# sparkfun-nrf52832-breakout.net
KiCad netlist of a schematic drawn in EAGLE
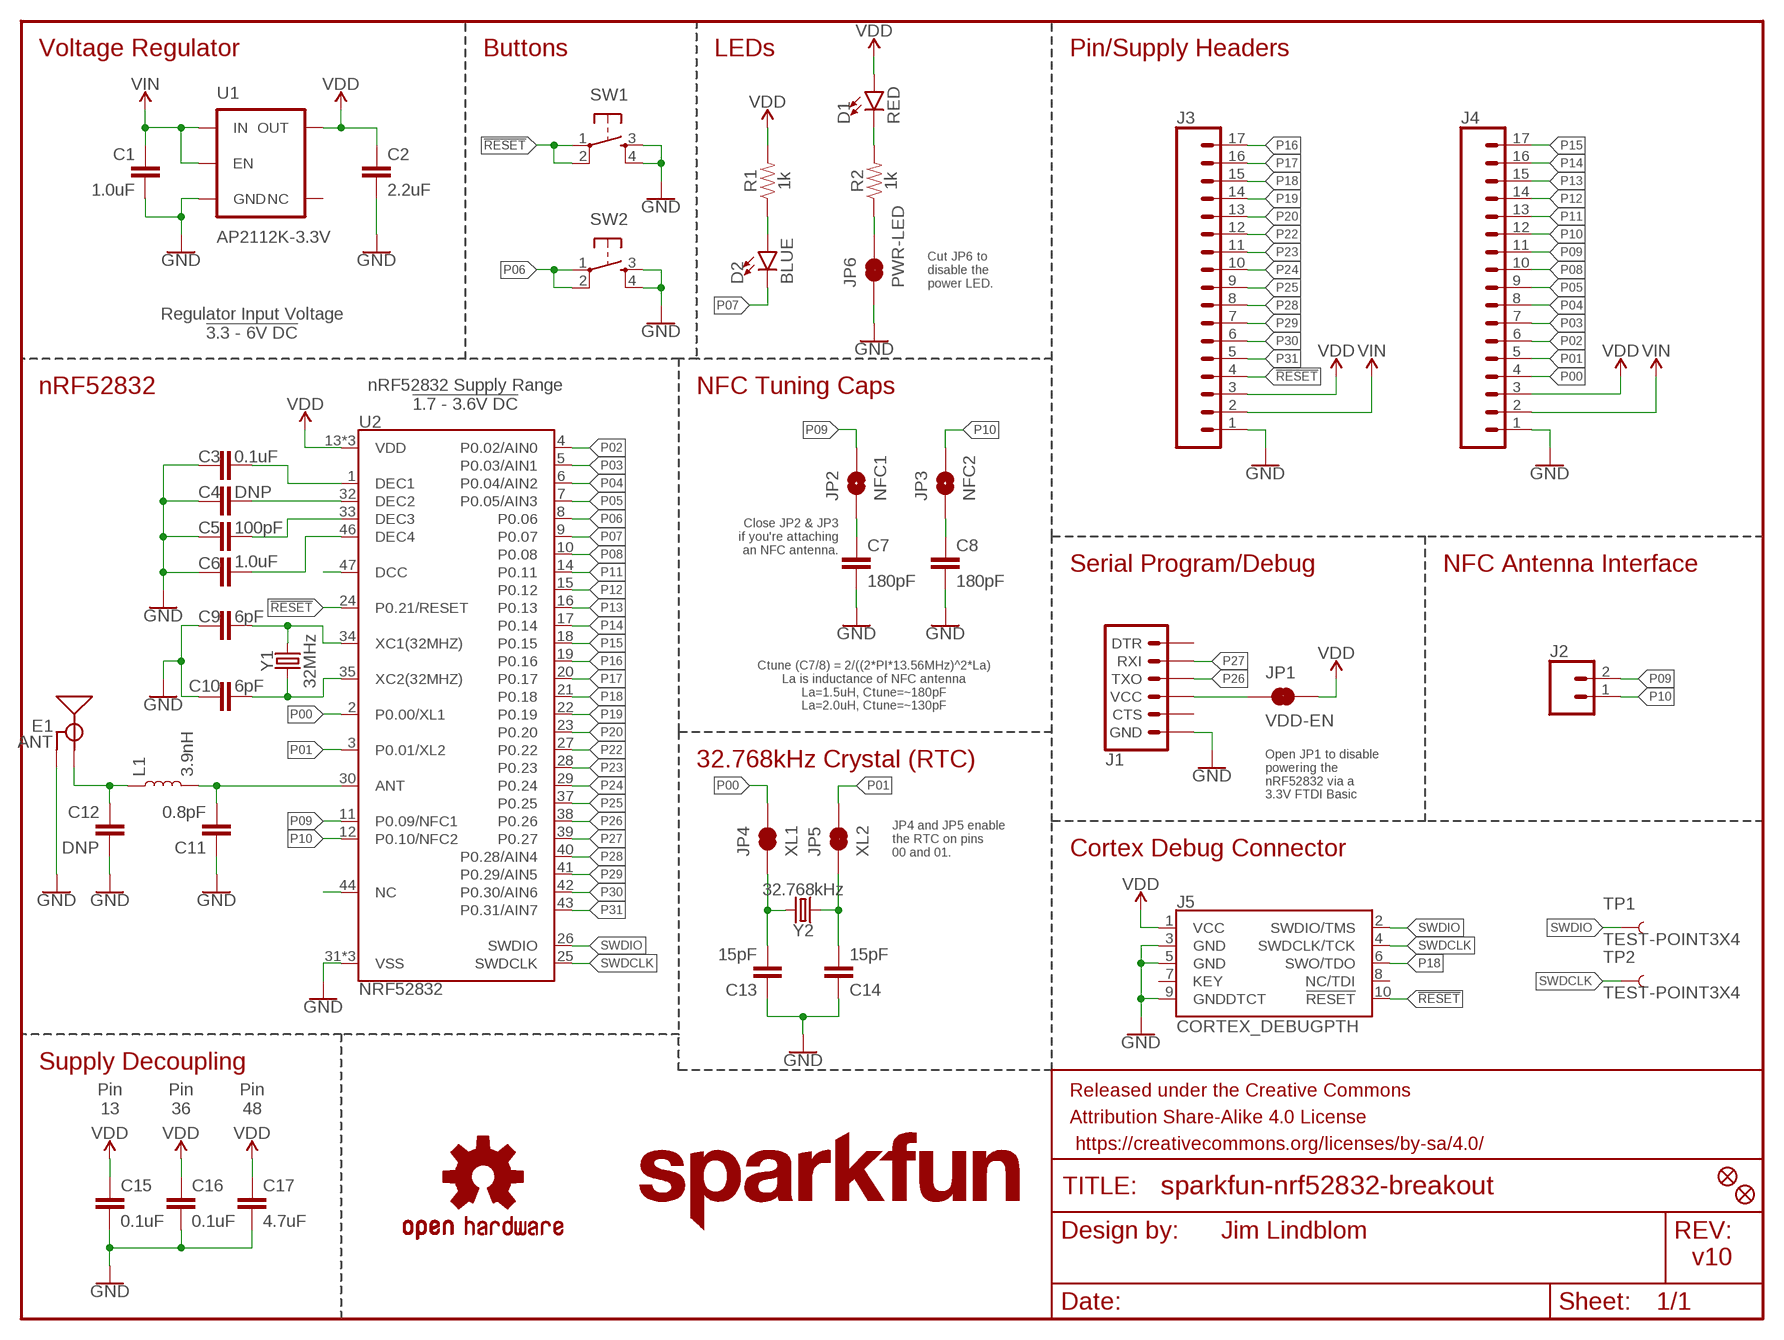
[diagram p0: schematic, sheet 1]

(export (version "E")
  (design (tool "Eeschema 10.0.6"))
  (components
    (comp (ref "C1")
      (value "1.0uF")
      (footprint "eagle-import:0603")
      (libsource (lib "eagle-import") (part "1.0UF-0603-16V-10%"))
    )
    (comp (ref "C2")
      (value "2.2uF")
      (footprint "eagle-import:0603")
      (libsource (lib "eagle-import") (part "2.2UF-0603-10V-20%"))
    )
    (comp (ref "C3")
      (value "0.1uF")
      (footprint "eagle-import:0402")
      (libsource (lib "eagle-import") (part "0.1UF-0402-16V-10%"))
    )
    (comp (ref "C4")
      (value "DNP")
      (footprint "eagle-import:0402")
      (libsource (lib "eagle-import") (part "CAP0402"))
    )
    (comp (ref "C5")
      (value "100pF")
      (footprint "eagle-import:0402")
      (libsource (lib "eagle-import") (part "100PF-0402-50V-5%"))
    )
    (comp (ref "C6")
      (value "1.0uF")
      (footprint "eagle-import:0402")
      (libsource (lib "eagle-import") (part "1.0UF-0402-16V-10%"))
    )
    (comp (ref "C7")
      (value "180pF")
      (footprint "eagle-import:0603")
      (libsource (lib "eagle-import") (part "180PF-0603-50V-5%"))
    )
    (comp (ref "C8")
      (value "180pF")
      (footprint "eagle-import:0603")
      (libsource (lib "eagle-import") (part "180PF-0603-50V-5%"))
    )
    (comp (ref "C9")
      (value "6pF")
      (footprint "eagle-import:0402")
      (libsource (lib "eagle-import") (part "6PF-0402-50V-0.5%"))
    )
    (comp (ref "C10")
      (value "6pF")
      (footprint "eagle-import:0402")
      (libsource (lib "eagle-import") (part "6PF-0402-50V-0.5%"))
    )
    (comp (ref "C11")
      (value "0.8pF")
      (footprint "eagle-import:0402")
      (libsource (lib "eagle-import") (part "0.8PF-0402-50V-0.1PF"))
    )
    (comp (ref "C12")
      (value "DNP")
      (footprint "eagle-import:0402")
      (libsource (lib "eagle-import") (part "CAP0402"))
    )
    (comp (ref "C13")
      (value "15pF")
      (footprint "eagle-import:0402")
      (libsource (lib "eagle-import") (part "15PF-0402-50V-5%"))
    )
    (comp (ref "C14")
      (value "15pF")
      (footprint "eagle-import:0402")
      (libsource (lib "eagle-import") (part "15PF-0402-50V-5%"))
    )
    (comp (ref "C15")
      (value "0.1uF")
      (footprint "eagle-import:0402")
      (libsource (lib "eagle-import") (part "0.1UF-0402-16V-10%"))
    )
    (comp (ref "C16")
      (value "0.1uF")
      (footprint "eagle-import:0402")
      (libsource (lib "eagle-import") (part "0.1UF-0402-16V-10%"))
    )
    (comp (ref "C17")
      (value "4.7uF")
      (footprint "eagle-import:0603")
      (libsource (lib "eagle-import") (part "4.7UF0603"))
    )
    (comp (ref "D1")
      (value "RED")
      (footprint "eagle-import:LED-0603")
      (libsource (lib "eagle-import") (part "LED-RED0603"))
    )
    (comp (ref "D2")
      (value "BLUE")
      (footprint "eagle-import:LED-0603")
      (libsource (lib "eagle-import") (part "LED-BLUE0603"))
    )
    (comp (ref "E1")
      (value "ANT")
      (footprint "eagle-import:TRACE_ANTENNA_2.4GHZ_15.2MM")
      (libsource (lib "eagle-import") (part "ANTENNA-GROUNDEDTRACE-15.2MM"))
    )
    (comp (ref "FD1")
      (value "FIDUCIALUFIDUCIAL")
      (footprint "eagle-import:FIDUCIAL-MICRO")
      (libsource (lib "eagle-import") (part "FIDUCIALUFIDUCIAL"))
    )
    (comp (ref "FD2")
      (value "FIDUCIALUFIDUCIAL")
      (footprint "eagle-import:FIDUCIAL-MICRO")
      (libsource (lib "eagle-import") (part "FIDUCIALUFIDUCIAL"))
    )
    (comp (ref "FRAME1")
      (value "FRAME-LETTER")
      (footprint "eagle-import:CREATIVE_COMMONS")
      (libsource (lib "eagle-import") (part "FRAME-LETTER"))
    )
    (comp (ref "J1")
      (value "ARDUINO_SERIAL_PROGRAMPTH")
      (footprint "eagle-import:1X06")
      (libsource (lib "eagle-import") (part "ARDUINO_SERIAL_PROGRAMPTH"))
    )
    (comp (ref "J2")
      (value "CONN_02PTH")
      (footprint "eagle-import:1X02")
      (libsource (lib "eagle-import") (part "CONN_02PTH"))
    )
    (comp (ref "J3")
      (value "CONN_17")
      (footprint "eagle-import:1X17")
      (libsource (lib "eagle-import") (part "CONN_17"))
    )
    (comp (ref "J4")
      (value "CONN_17")
      (footprint "eagle-import:1X17")
      (libsource (lib "eagle-import") (part "CONN_17"))
    )
    (comp (ref "J5")
      (value "CORTEX_DEBUGPTH")
      (footprint "eagle-import:2X5-PTH-1.27MM")
      (libsource (lib "eagle-import") (part "CORTEX_DEBUGPTH"))
    )
    (comp (ref "JP1")
      (value "VDD-EN")
      (footprint "eagle-import:SMT-JUMPER_2_NC_TRACE_SILK")
      (libsource (lib "eagle-import") (part "JUMPER-SMT_2_NC_TRACE_SILK"))
    )
    (comp (ref "JP2")
      (value "NFC1")
      (footprint "eagle-import:SMT-JUMPER_2_NO_SILK")
      (libsource (lib "eagle-import") (part "JUMPER-SMT_2_NO_SILK"))
    )
    (comp (ref "JP3")
      (value "NFC2")
      (footprint "eagle-import:SMT-JUMPER_2_NO_SILK")
      (libsource (lib "eagle-import") (part "JUMPER-SMT_2_NO_SILK"))
    )
    (comp (ref "JP4")
      (value "XL1")
      (footprint "eagle-import:PAD-JUMPER-2-NC_BY_TRACE_YES_SILK")
      (libsource (lib "eagle-import") (part "JUMPER-PAD-2-NC_BY_TRACE"))
    )
    (comp (ref "JP5")
      (value "XL2")
      (footprint "eagle-import:PAD-JUMPER-2-NC_BY_TRACE_YES_SILK")
      (libsource (lib "eagle-import") (part "JUMPER-PAD-2-NC_BY_TRACE"))
    )
    (comp (ref "JP6")
      (value "PWR-LED")
      (footprint "eagle-import:PAD-JUMPER-2-NC_BY_TRACE_YES_SILK")
      (libsource (lib "eagle-import") (part "JUMPER-PAD-2-NC_BY_TRACE"))
    )
    (comp (ref "L1")
      (value "3.9nH")
      (footprint "eagle-import:0402")
      (libsource (lib "eagle-import") (part "INDUCTOR-0402-3.9NH"))
    )
    (comp (ref "LOGO1")
      (value "OSHW-LOGOMINI")
      (footprint "eagle-import:OSHW-LOGO-MINI")
      (libsource (lib "eagle-import") (part "OSHW-LOGOMINI"))
    )
    (comp (ref "LOGO2")
      (value "SFE_LOGO_NAME.1_INCH")
      (footprint "eagle-import:SFE_LOGO_NAME_.1")
      (libsource (lib "eagle-import") (part "SFE_LOGO_NAME.1_INCH"))
    )
    (comp (ref "LOGO3")
      (value "SFE_LOGO_NAME.1_INCH")
      (footprint "eagle-import:SFE_LOGO_NAME_.1")
      (libsource (lib "eagle-import") (part "SFE_LOGO_NAME.1_INCH"))
    )
    (comp (ref "R1")
      (value "1k")
      (footprint "eagle-import:0603")
      (libsource (lib "eagle-import") (part "1KOHM-0603-1/10W-1%"))
    )
    (comp (ref "R2")
      (value "1k")
      (footprint "eagle-import:0603")
      (libsource (lib "eagle-import") (part "1KOHM-0603-1/10W-1%"))
    )
    (comp (ref "SW1")
      (value "SWITCH_SPST_4_PINRECT")
      (footprint "eagle-import:TACTILE_SWITCH_SMD_4.6X2.8MM")
      (libsource (lib "eagle-import") (part "SWITCH_SPST_4_PINRECT"))
    )
    (comp (ref "SW2")
      (value "SWITCH_SPST_4_PINRECT")
      (footprint "eagle-import:TACTILE_SWITCH_SMD_4.6X2.8MM")
      (libsource (lib "eagle-import") (part "SWITCH_SPST_4_PINRECT"))
    )
    (comp (ref "TP1")
      (value "TEST-POINT3X4")
      (footprint "eagle-import:PAD.03X.04")
      (libsource (lib "eagle-import") (part "TEST-POINT3X4"))
    )
    (comp (ref "TP2")
      (value "TEST-POINT3X4")
      (footprint "eagle-import:PAD.03X.04")
      (libsource (lib "eagle-import") (part "TEST-POINT3X4"))
    )
    (comp (ref "U1")
      (value "AP2112K-3.3V")
      (footprint "eagle-import:SOT23-5")
      (libsource (lib "eagle-import") (part "V_REG_AP2112K-3.3V"))
    )
    (comp (ref "U2")
      (value "NRF52832")
      (footprint "eagle-import:QFN48-6X6MM")
      (libsource (lib "eagle-import") (part "NRF52832"))
    )
    (comp (ref "Y1")
      (value "32MHz")
      (footprint "eagle-import:CRYSTAL-SMD-2.0X1.6MM")
      (libsource (lib "eagle-import") (part "CRYSTAL-32MHZ-SMD-2.0X1.6MM"))
    )
    (comp (ref "Y2")
      (value "32.768kHz")
      (footprint "eagle-import:CRYSTAL-SMD-3.2X1.5MM")
      (libsource (lib "eagle-import") (part "CRYSTAL-32.768KHZSMD-3.2X1.5"))
    )
  )
  (nets
    (net (code "1") (name "/~{RESET}") (class "Default")
      (node (ref "J3") (pin "4") (pinfunction "4_4") (pintype "passive"))
      (node (ref "J5") (pin "10") (pinfunction "~{RESET}_10") (pintype "bidirectional"))
      (node (ref "SW1") (pin "1") (pinfunction "1_1") (pintype "passive"))
      (node (ref "SW1") (pin "2") (pinfunction "2_2") (pintype "passive"))
      (node (ref "U2") (pin "24") (pinfunction "P0.21/RESET_24") (pintype "bidirectional"))
    )
    (net (code "2") (name "GND") (class "Default")
      (node (ref "C1") (pin "2") (pinfunction "2_2") (pintype "passive"))
      (node (ref "C10") (pin "2") (pinfunction "2_2") (pintype "passive"))
      (node (ref "C11") (pin "1") (pinfunction "1_1") (pintype "passive"))
      (node (ref "C12") (pin "2") (pinfunction "2_2") (pintype "passive"))
      (node (ref "C13") (pin "1") (pinfunction "1_1") (pintype "passive"))
      (node (ref "C14") (pin "1") (pinfunction "1_1") (pintype "passive"))
      (node (ref "C15") (pin "2") (pinfunction "2_2") (pintype "passive"))
      (node (ref "C16") (pin "2") (pinfunction "2_2") (pintype "passive"))
      (node (ref "C17") (pin "2") (pinfunction "2_2") (pintype "passive"))
      (node (ref "C2") (pin "2") (pinfunction "2_2") (pintype "passive"))
      (node (ref "C3") (pin "1") (pinfunction "1_1") (pintype "passive"))
      (node (ref "C4") (pin "1") (pinfunction "1_1") (pintype "passive"))
      (node (ref "C5") (pin "1") (pinfunction "1_1") (pintype "passive"))
      (node (ref "C6") (pin "1") (pinfunction "1_1") (pintype "passive"))
      (node (ref "C7") (pin "2") (pinfunction "2_2") (pintype "passive"))
      (node (ref "C8") (pin "2") (pinfunction "2_2") (pintype "passive"))
      (node (ref "C9") (pin "1") (pinfunction "1_1") (pintype "passive"))
      (node (ref "E1") (pin "GND") (pinfunction "GND_GND") (pintype "bidirectional"))
      (node (ref "J1") (pin "6") (pinfunction "GND_6") (pintype "passive"))
      (node (ref "J3") (pin "1") (pinfunction "1_1") (pintype "passive"))
      (node (ref "J4") (pin "1") (pinfunction "1_1") (pintype "passive"))
      (node (ref "J5") (pin "3") (pinfunction "GND_3") (pintype "bidirectional"))
      (node (ref "J5") (pin "5") (pinfunction "GND_5") (pintype "bidirectional"))
      (node (ref "J5") (pin "9") (pinfunction "GNDDTCT_9") (pintype "bidirectional"))
      (node (ref "JP6") (pin "1") (pinfunction "1_1") (pintype "passive"))
      (node (ref "SW1") (pin "3") (pinfunction "3_3") (pintype "passive"))
      (node (ref "SW1") (pin "4") (pinfunction "4_4") (pintype "passive"))
      (node (ref "SW2") (pin "3") (pinfunction "3_3") (pintype "passive"))
      (node (ref "SW2") (pin "4") (pinfunction "4_4") (pintype "passive"))
      (node (ref "U1") (pin "2") (pinfunction "GND_2") (pintype "input"))
      (node (ref "U2") (pin "31") (pinfunction "VSS_31") (pintype "bidirectional"))
      (node (ref "U2") (pin "45") (pinfunction "VSS_45") (pintype "bidirectional"))
      (node (ref "U2") (pin "EP") (pinfunction "VSS_EP") (pintype "bidirectional"))
    )
    (net (code "3") (name "Net-(C7-Pad1)") (class "Default")
      (node (ref "C7") (pin "1") (pinfunction "1_1") (pintype "passive"))
      (node (ref "JP2") (pin "1") (pinfunction "1_1") (pintype "passive"))
    )
    (net (code "4") (name "Net-(C8-Pad1)") (class "Default")
      (node (ref "C8") (pin "1") (pinfunction "1_1") (pintype "passive"))
      (node (ref "JP3") (pin "1") (pinfunction "1_1") (pintype "passive"))
    )
    (net (code "5") (name "Net-(D1-PadC)") (class "Default")
      (node (ref "D1") (pin "C") (pinfunction "C_C") (pintype "passive"))
      (node (ref "R2") (pin "2") (pinfunction "2_2") (pintype "passive"))
    )
    (net (code "6") (name "Net-(D2-PadA)") (class "Default")
      (node (ref "D2") (pin "A") (pinfunction "A_A") (pintype "passive"))
      (node (ref "R1") (pin "1") (pinfunction "1_1") (pintype "passive"))
    )
    (net (code "7") (name "Net-(E1-SIGNAL)") (class "Default")
      (node (ref "C12") (pin "1") (pinfunction "1_1") (pintype "passive"))
      (node (ref "E1") (pin "ANT") (pinfunction "SIGNAL_ANT") (pintype "bidirectional"))
      (node (ref "L1") (pin "1") (pinfunction "1_1") (pintype "passive"))
    )
    (net (code "8") (name "Net-(J1-VCC)") (class "Default")
      (node (ref "J1") (pin "4") (pinfunction "VCC_4") (pintype "passive"))
      (node (ref "JP1") (pin "1") (pinfunction "1_1") (pintype "passive"))
    )
    (net (code "9") (name "Net-(JP6-Pad2)") (class "Default")
      (node (ref "JP6") (pin "2") (pinfunction "2_2") (pintype "passive"))
      (node (ref "R2") (pin "1") (pinfunction "1_1") (pintype "passive"))
    )
    (net (code "10") (name "Net-(U2-ANT)") (class "Default")
      (node (ref "C11") (pin "2") (pinfunction "2_2") (pintype "passive"))
      (node (ref "L1") (pin "2") (pinfunction "2_2") (pintype "passive"))
      (node (ref "U2") (pin "30") (pinfunction "ANT_30") (pintype "bidirectional"))
    )
    (net (code "11") (name "Net-(U2-DEC1)") (class "Default")
      (node (ref "C3") (pin "2") (pinfunction "2_2") (pintype "passive"))
      (node (ref "U2") (pin "1") (pinfunction "DEC1_1") (pintype "bidirectional"))
    )
    (net (code "12") (name "Net-(U2-DEC2)") (class "Default")
      (node (ref "C4") (pin "2") (pinfunction "2_2") (pintype "passive"))
      (node (ref "U2") (pin "32") (pinfunction "DEC2_32") (pintype "bidirectional"))
    )
    (net (code "13") (name "Net-(U2-DEC3)") (class "Default")
      (node (ref "C5") (pin "2") (pinfunction "2_2") (pintype "passive"))
      (node (ref "U2") (pin "33") (pinfunction "DEC3_33") (pintype "bidirectional"))
    )
    (net (code "14") (name "Net-(U2-DEC4)") (class "Default")
      (node (ref "C6") (pin "2") (pinfunction "2_2") (pintype "passive"))
      (node (ref "U2") (pin "46") (pinfunction "DEC4_46") (pintype "bidirectional"))
    )
    (net (code "15") (name "Net-(U2-XC1(32MHZ))") (class "Default")
      (node (ref "C9") (pin "2") (pinfunction "2_2") (pintype "passive"))
      (node (ref "U2") (pin "34") (pinfunction "XC1(32MHZ)_34") (pintype "bidirectional"))
      (node (ref "Y1") (pin "3") (pinfunction "2_3") (pintype "passive"))
    )
    (net (code "16") (name "Net-(U2-XC2(32MHZ))") (class "Default")
      (node (ref "C10") (pin "1") (pinfunction "1_1") (pintype "passive"))
      (node (ref "U2") (pin "35") (pinfunction "XC2(32MHZ)_35") (pintype "bidirectional"))
      (node (ref "Y1") (pin "1") (pinfunction "1_1") (pintype "passive"))
    )
    (net (code "17") (name "Net-(Y2-1)") (class "Default")
      (node (ref "C14") (pin "2") (pinfunction "2_2") (pintype "passive"))
      (node (ref "JP5") (pin "1") (pinfunction "1_1") (pintype "passive"))
      (node (ref "Y2") (pin "P$1") (pinfunction "1_P$1") (pintype "passive"))
    )
    (net (code "18") (name "Net-(Y2-2)") (class "Default")
      (node (ref "C13") (pin "2") (pinfunction "2_2") (pintype "passive"))
      (node (ref "JP4") (pin "1") (pinfunction "1_1") (pintype "passive"))
      (node (ref "Y2") (pin "P$2") (pinfunction "2_P$2") (pintype "passive"))
    )
    (net (code "19") (name "P00") (class "Default")
      (node (ref "J4") (pin "4") (pinfunction "4_4") (pintype "passive"))
      (node (ref "JP4") (pin "2") (pinfunction "2_2") (pintype "passive"))
      (node (ref "U2") (pin "2") (pinfunction "P0.00/XL1_2") (pintype "bidirectional"))
    )
    (net (code "20") (name "P01") (class "Default")
      (node (ref "J4") (pin "5") (pinfunction "5_5") (pintype "passive"))
      (node (ref "JP5") (pin "2") (pinfunction "2_2") (pintype "passive"))
      (node (ref "U2") (pin "3") (pinfunction "P0.01/XL2_3") (pintype "bidirectional"))
    )
    (net (code "21") (name "P02") (class "Default")
      (node (ref "J4") (pin "6") (pinfunction "6_6") (pintype "passive"))
      (node (ref "U2") (pin "4") (pinfunction "P0.02/AIN0_4") (pintype "bidirectional"))
    )
    (net (code "22") (name "P03") (class "Default")
      (node (ref "J4") (pin "7") (pinfunction "7_7") (pintype "passive"))
      (node (ref "U2") (pin "5") (pinfunction "P0.03/AIN1_5") (pintype "bidirectional"))
    )
    (net (code "23") (name "P04") (class "Default")
      (node (ref "J4") (pin "8") (pinfunction "8_8") (pintype "passive"))
      (node (ref "U2") (pin "6") (pinfunction "P0.04/AIN2_6") (pintype "bidirectional"))
    )
    (net (code "24") (name "P05") (class "Default")
      (node (ref "J4") (pin "9") (pinfunction "9_9") (pintype "passive"))
      (node (ref "U2") (pin "7") (pinfunction "P0.05/AIN3_7") (pintype "bidirectional"))
    )
    (net (code "25") (name "P06") (class "Default")
      (node (ref "SW2") (pin "1") (pinfunction "1_1") (pintype "passive"))
      (node (ref "SW2") (pin "2") (pinfunction "2_2") (pintype "passive"))
      (node (ref "U2") (pin "8") (pinfunction "P0.06_8") (pintype "bidirectional"))
    )
    (net (code "26") (name "P07") (class "Default")
      (node (ref "D2") (pin "C") (pinfunction "C_C") (pintype "passive"))
      (node (ref "U2") (pin "9") (pinfunction "P0.07_9") (pintype "bidirectional"))
    )
    (net (code "27") (name "P08") (class "Default")
      (node (ref "J4") (pin "10") (pinfunction "10_10") (pintype "passive"))
      (node (ref "U2") (pin "10") (pinfunction "P0.08_10") (pintype "bidirectional"))
    )
    (net (code "28") (name "P09") (class "Default")
      (node (ref "J2") (pin "2") (pinfunction "2_2") (pintype "passive"))
      (node (ref "J4") (pin "11") (pinfunction "11_11") (pintype "passive"))
      (node (ref "JP2") (pin "2") (pinfunction "2_2") (pintype "passive"))
      (node (ref "U2") (pin "11") (pinfunction "P0.09/NFC1_11") (pintype "bidirectional"))
    )
    (net (code "29") (name "P10") (class "Default")
      (node (ref "J2") (pin "1") (pinfunction "1_1") (pintype "passive"))
      (node (ref "J4") (pin "12") (pinfunction "12_12") (pintype "passive"))
      (node (ref "JP3") (pin "2") (pinfunction "2_2") (pintype "passive"))
      (node (ref "U2") (pin "12") (pinfunction "P0.10/NFC2_12") (pintype "bidirectional"))
    )
    (net (code "30") (name "P11") (class "Default")
      (node (ref "J4") (pin "13") (pinfunction "13_13") (pintype "passive"))
      (node (ref "U2") (pin "14") (pinfunction "P0.11_14") (pintype "bidirectional"))
    )
    (net (code "31") (name "P12") (class "Default")
      (node (ref "J4") (pin "14") (pinfunction "14_14") (pintype "passive"))
      (node (ref "U2") (pin "15") (pinfunction "P0.12_15") (pintype "bidirectional"))
    )
    (net (code "32") (name "P13") (class "Default")
      (node (ref "J4") (pin "15") (pinfunction "15_15") (pintype "passive"))
      (node (ref "U2") (pin "16") (pinfunction "P0.13_16") (pintype "bidirectional"))
    )
    (net (code "33") (name "P14") (class "Default")
      (node (ref "J4") (pin "16") (pinfunction "16_16") (pintype "passive"))
      (node (ref "U2") (pin "17") (pinfunction "P0.14_17") (pintype "bidirectional"))
    )
    (net (code "34") (name "P15") (class "Default")
      (node (ref "J4") (pin "17") (pinfunction "17_17") (pintype "passive"))
      (node (ref "U2") (pin "18") (pinfunction "P0.15_18") (pintype "bidirectional"))
    )
    (net (code "35") (name "P16") (class "Default")
      (node (ref "J3") (pin "17") (pinfunction "17_17") (pintype "passive"))
      (node (ref "U2") (pin "19") (pinfunction "P0.16_19") (pintype "bidirectional"))
    )
    (net (code "36") (name "P17") (class "Default")
      (node (ref "J3") (pin "16") (pinfunction "16_16") (pintype "passive"))
      (node (ref "U2") (pin "20") (pinfunction "P0.17_20") (pintype "bidirectional"))
    )
    (net (code "37") (name "P18") (class "Default")
      (node (ref "J3") (pin "15") (pinfunction "15_15") (pintype "passive"))
      (node (ref "J5") (pin "6") (pinfunction "SWO/TDO_6") (pintype "bidirectional"))
      (node (ref "U2") (pin "21") (pinfunction "P0.18_21") (pintype "bidirectional"))
    )
    (net (code "38") (name "P19") (class "Default")
      (node (ref "J3") (pin "14") (pinfunction "14_14") (pintype "passive"))
      (node (ref "U2") (pin "22") (pinfunction "P0.19_22") (pintype "bidirectional"))
    )
    (net (code "39") (name "P20") (class "Default")
      (node (ref "J3") (pin "13") (pinfunction "13_13") (pintype "passive"))
      (node (ref "U2") (pin "23") (pinfunction "P0.20_23") (pintype "bidirectional"))
    )
    (net (code "40") (name "P22") (class "Default")
      (node (ref "J3") (pin "12") (pinfunction "12_12") (pintype "passive"))
      (node (ref "U2") (pin "27") (pinfunction "P0.22_27") (pintype "bidirectional"))
    )
    (net (code "41") (name "P23") (class "Default")
      (node (ref "J3") (pin "11") (pinfunction "11_11") (pintype "passive"))
      (node (ref "U2") (pin "28") (pinfunction "P0.23_28") (pintype "bidirectional"))
    )
    (net (code "42") (name "P24") (class "Default")
      (node (ref "J3") (pin "10") (pinfunction "10_10") (pintype "passive"))
      (node (ref "U2") (pin "29") (pinfunction "P0.24_29") (pintype "bidirectional"))
    )
    (net (code "43") (name "P25") (class "Default")
      (node (ref "J3") (pin "9") (pinfunction "9_9") (pintype "passive"))
      (node (ref "U2") (pin "37") (pinfunction "P0.25_37") (pintype "bidirectional"))
    )
    (net (code "44") (name "P26") (class "Default")
      (node (ref "J1") (pin "3") (pinfunction "TXO_3") (pintype "passive"))
      (node (ref "U2") (pin "38") (pinfunction "P0.26_38") (pintype "bidirectional"))
    )
    (net (code "45") (name "P27") (class "Default")
      (node (ref "J1") (pin "2") (pinfunction "RXI_2") (pintype "passive"))
      (node (ref "U2") (pin "39") (pinfunction "P0.27_39") (pintype "bidirectional"))
    )
    (net (code "46") (name "P28") (class "Default")
      (node (ref "J3") (pin "8") (pinfunction "8_8") (pintype "passive"))
      (node (ref "U2") (pin "40") (pinfunction "P0.28/AIN4_40") (pintype "bidirectional"))
    )
    (net (code "47") (name "P29") (class "Default")
      (node (ref "J3") (pin "7") (pinfunction "7_7") (pintype "passive"))
      (node (ref "U2") (pin "41") (pinfunction "P0.29/AIN5_41") (pintype "bidirectional"))
    )
    (net (code "48") (name "P30") (class "Default")
      (node (ref "J3") (pin "6") (pinfunction "6_6") (pintype "passive"))
      (node (ref "U2") (pin "42") (pinfunction "P0.30/AIN6_42") (pintype "bidirectional"))
    )
    (net (code "49") (name "P31") (class "Default")
      (node (ref "J3") (pin "5") (pinfunction "5_5") (pintype "passive"))
      (node (ref "U2") (pin "43") (pinfunction "P0.31/AIN7_43") (pintype "bidirectional"))
    )
    (net (code "50") (name "SWDCLK") (class "Default")
      (node (ref "J5") (pin "4") (pinfunction "SWDCLK/TCK_4") (pintype "bidirectional"))
      (node (ref "TP2") (pin "P$1") (pinfunction "1_P$1") (pintype "bidirectional"))
      (node (ref "U2") (pin "25") (pinfunction "SWDCLK_25") (pintype "bidirectional"))
    )
    (net (code "51") (name "SWDIO") (class "Default")
      (node (ref "J5") (pin "2") (pinfunction "SWDIO/TMS_2") (pintype "bidirectional"))
      (node (ref "TP1") (pin "P$1") (pinfunction "1_P$1") (pintype "bidirectional"))
      (node (ref "U2") (pin "26") (pinfunction "SWDIO_26") (pintype "bidirectional"))
    )
    (net (code "52") (name "VDD") (class "Default")
      (node (ref "C15") (pin "1") (pinfunction "1_1") (pintype "passive"))
      (node (ref "C16") (pin "1") (pinfunction "1_1") (pintype "passive"))
      (node (ref "C17") (pin "1") (pinfunction "1_1") (pintype "passive"))
      (node (ref "C2") (pin "1") (pinfunction "1_1") (pintype "passive"))
      (node (ref "D1") (pin "A") (pinfunction "A_A") (pintype "passive"))
      (node (ref "J3") (pin "3") (pinfunction "3_3") (pintype "passive"))
      (node (ref "J4") (pin "3") (pinfunction "3_3") (pintype "passive"))
      (node (ref "J5") (pin "1") (pinfunction "VCC_1") (pintype "bidirectional"))
      (node (ref "JP1") (pin "2") (pinfunction "2_2") (pintype "passive"))
      (node (ref "R1") (pin "2") (pinfunction "2_2") (pintype "passive"))
      (node (ref "U1") (pin "5") (pinfunction "OUT_5") (pintype "passive"))
      (node (ref "U2") (pin "13") (pinfunction "VDD_13") (pintype "bidirectional"))
      (node (ref "U2") (pin "36") (pinfunction "VDD_36") (pintype "bidirectional"))
      (node (ref "U2") (pin "48") (pinfunction "VDD_48") (pintype "bidirectional"))
    )
    (net (code "53") (name "VIN") (class "Default")
      (node (ref "C1") (pin "1") (pinfunction "1_1") (pintype "passive"))
      (node (ref "J3") (pin "2") (pinfunction "2_2") (pintype "passive"))
      (node (ref "J4") (pin "2") (pinfunction "2_2") (pintype "passive"))
      (node (ref "U1") (pin "1") (pinfunction "IN_1") (pintype "input"))
      (node (ref "U1") (pin "3") (pinfunction "EN_3") (pintype "input"))
    )
    (net (code "54") (name "unconnected-(J1-CTS-Pad5)") (class "Default")
      (node (ref "J1") (pin "5") (pinfunction "CTS_5") (pintype "passive"))
    )
    (net (code "55") (name "unconnected-(J1-DTR-Pad1)") (class "Default")
      (node (ref "J1") (pin "1") (pinfunction "DTR_1") (pintype "passive"))
    )
    (net (code "56") (name "unconnected-(J5-KEY-Pad7)") (class "Default")
      (node (ref "J5") (pin "7") (pinfunction "KEY_7") (pintype "bidirectional"))
    )
    (net (code "57") (name "unconnected-(J5-NC{slash}TDI-Pad8)") (class "Default")
      (node (ref "J5") (pin "8") (pinfunction "NC/TDI_8") (pintype "bidirectional"))
    )
    (net (code "58") (name "unconnected-(U1-NC-Pad4)") (class "Default")
      (node (ref "U1") (pin "4") (pinfunction "NC_4") (pintype "input"))
    )
    (net (code "59") (name "unconnected-(U2-DCC-Pad47)") (class "Default")
      (node (ref "U2") (pin "47") (pinfunction "DCC_47") (pintype "bidirectional"))
    )
    (net (code "60") (name "unconnected-(U2-NC-Pad44)") (class "Default")
      (node (ref "U2") (pin "44") (pinfunction "NC_44") (pintype "bidirectional"))
    )
  )
)
